# power.net
KiCad netlist of a schematic drawn in Altium Designer
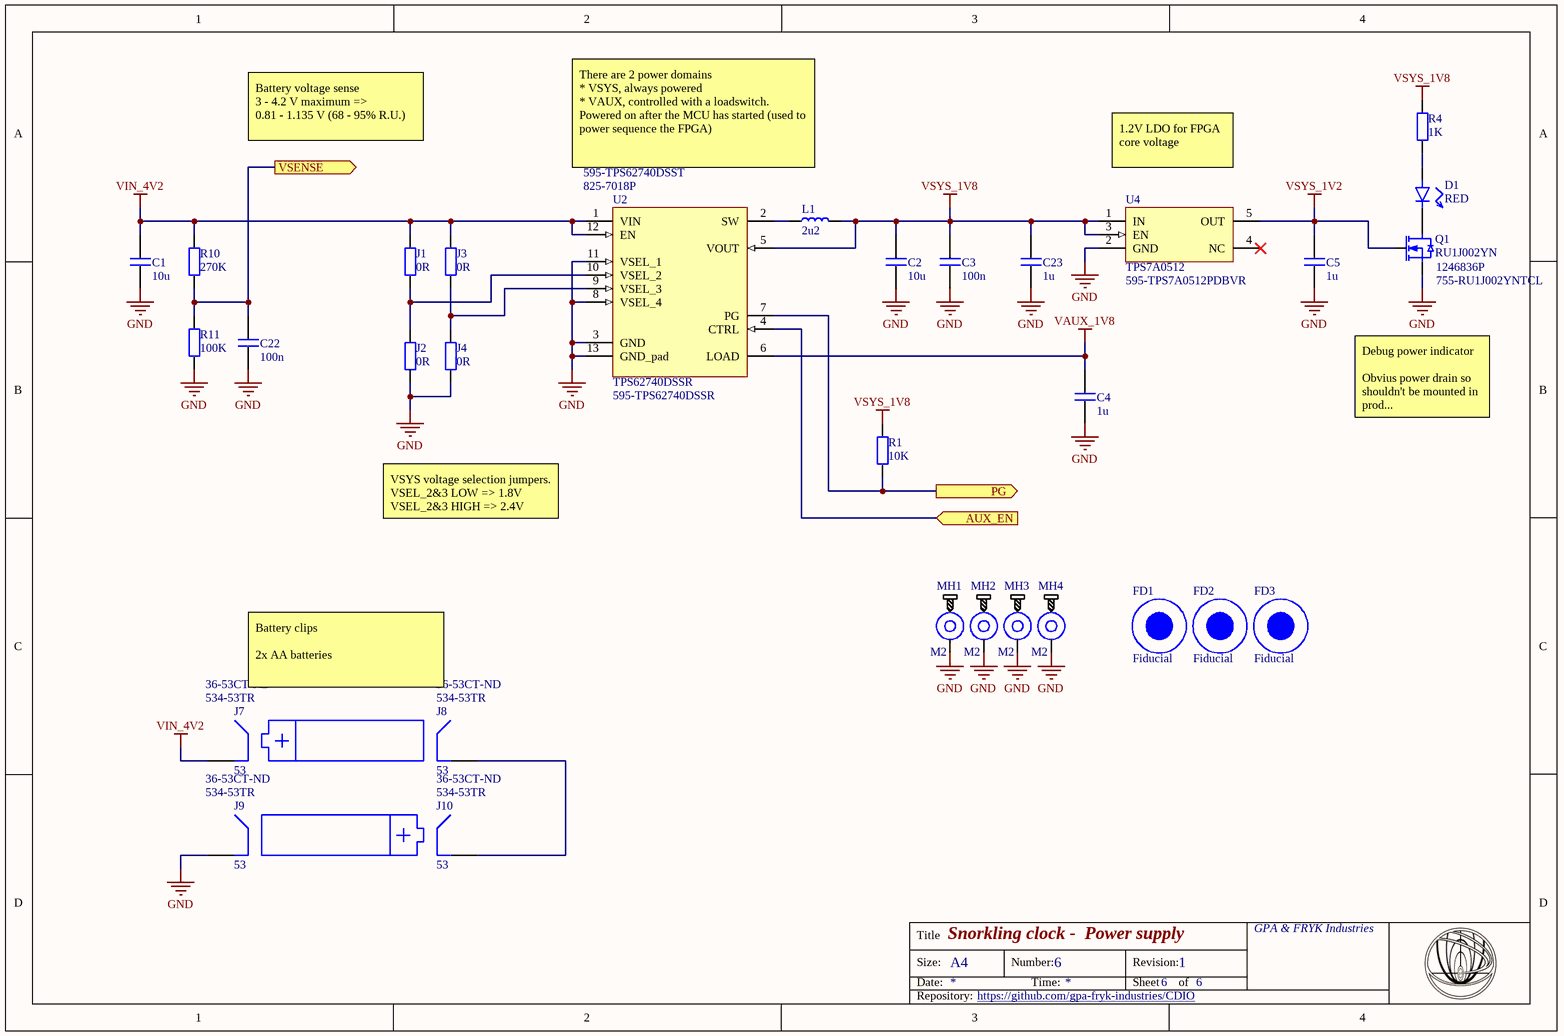
[diagram p0: power.SchDoc]

(export (version "E")
  (design (tool "Eeschema 10.0.6"))
  (components
    (comp (ref "C1")
      (value "10u")
      (footprint "CAPC3216X14N")
      (description "Capacitor")
      (fields (field (name "Comment") "cap"))
      (libsource (lib "lib_passives") (part "cap"))
    )
    (comp (ref "C2")
      (value "10u")
      (footprint "CAPC3216X14N")
      (description "Capacitor")
      (fields (field (name "Comment") "cap"))
      (libsource (lib "lib_passives") (part "cap"))
    )
    (comp (ref "C3")
      (value "100n")
      (footprint "CAPC1005X06N")
      (description "Capacitor")
      (fields (field (name "Comment") "cap"))
      (libsource (lib "lib_passives") (part "cap"))
    )
    (comp (ref "C4")
      (value "1u")
      (footprint "CAPC2012X11N")
      (description "Capacitor")
      (fields (field (name "Comment") "cap"))
      (libsource (lib "lib_passives") (part "cap"))
    )
    (comp (ref "C5")
      (value "1u")
      (footprint "CAPC2012X11N")
      (description "Capacitor")
      (fields (field (name "Comment") "cap"))
      (libsource (lib "lib_passives") (part "cap"))
    )
    (comp (ref "C22")
      (value "100n")
      (footprint "CAPC1005X06N")
      (description "Capacitor")
      (fields (field (name "Comment") "cap"))
      (libsource (lib "lib_passives") (part "cap"))
    )
    (comp (ref "C23")
      (value "1u")
      (footprint "CAPC2012X11N")
      (description "Capacitor")
      (fields (field (name "Comment") "cap"))
      (libsource (lib "lib_passives") (part "cap"))
    )
    (comp (ref "D1")
      (value "RED")
      (footprint "CAPCP1005X06N")
      (description "LED")
      (fields (field (name "Comment") "led"))
      (libsource (lib "lib_actives") (part "led"))
    )
    (comp (ref "FD1")
      (value "Fiducial")
      (footprint "fiducial_1_3")
      (libsource (lib "lib_mechanical") (part "fiducial"))
    )
    (comp (ref "FD2")
      (value "Fiducial")
      (footprint "fiducial_1_3")
      (libsource (lib "lib_mechanical") (part "fiducial"))
    )
    (comp (ref "FD3")
      (value "Fiducial")
      (footprint "fiducial_1_3")
      (libsource (lib "lib_mechanical") (part "fiducial"))
    )
    (comp (ref "J1")
      (value "0R")
      (footprint "RESC1005X04N")
      (description "Resistor")
      (fields (field (name "Comment") "res"))
      (libsource (lib "lib_passives") (part "res"))
    )
    (comp (ref "J2")
      (value "0R")
      (footprint "RESC1005X04N")
      (description "Resistor")
      (fields (field (name "Comment") "res"))
      (libsource (lib "lib_passives") (part "res"))
    )
    (comp (ref "J3")
      (value "0R")
      (footprint "RESC1005X04N")
      (description "Resistor")
      (fields (field (name "Comment") "res"))
      (libsource (lib "lib_passives") (part "res"))
    )
    (comp (ref "J4")
      (value "0R")
      (footprint "RESC1005X04N")
      (description "Resistor")
      (fields (field (name "Comment") "res"))
      (libsource (lib "lib_passives") (part "res"))
    )
    (comp (ref "J7")
      (value "53")
      (footprint "ke53")
      (description "Cylindrical Battery Contacts, Clips, Holders & Springs SMT Battery clip FOR AA")
      (fields
        (field (name "SUPPLIER PART NUMBER 1") "534-53TR")
        (field (name "SUPPLIER PART NUMBER 2") "36-53CT-ND")
      )
      (libsource (lib "lib_keystone") (part "ke53"))
    )
    (comp (ref "J8")
      (value "53")
      (footprint "ke53")
      (description "Cylindrical Battery Contacts, Clips, Holders & Springs SMT Battery clip FOR AA")
      (fields
        (field (name "SUPPLIER PART NUMBER 1") "534-53TR")
        (field (name "SUPPLIER PART NUMBER 2") "36-53CT-ND")
      )
      (libsource (lib "lib_keystone") (part "ke53"))
    )
    (comp (ref "J9")
      (value "53")
      (footprint "ke53")
      (description "Cylindrical Battery Contacts, Clips, Holders & Springs SMT Battery clip FOR AA")
      (fields
        (field (name "SUPPLIER PART NUMBER 1") "534-53TR")
        (field (name "SUPPLIER PART NUMBER 2") "36-53CT-ND")
      )
      (libsource (lib "lib_keystone") (part "ke53"))
    )
    (comp (ref "J10")
      (value "53")
      (footprint "ke53")
      (description "Cylindrical Battery Contacts, Clips, Holders & Springs SMT Battery clip FOR AA")
      (fields
        (field (name "SUPPLIER PART NUMBER 1") "534-53TR")
        (field (name "SUPPLIER PART NUMBER 2") "36-53CT-ND")
      )
      (libsource (lib "lib_keystone") (part "ke53"))
    )
    (comp (ref "L1")
      (value "2u2")
      (footprint "INDC3216X20N")
      (description "Inductor")
      (fields (field (name "Comment") "ind"))
      (libsource (lib "lib_passives") (part "ind"))
    )
    (comp (ref "MH1")
      (value "M2")
      (footprint "mount_m2l")
      (description "Mounting hole")
      (libsource (lib "lib_mechanical") (part "mounting_hole"))
    )
    (comp (ref "MH2")
      (value "M2")
      (footprint "mount_m2l")
      (description "Mounting hole")
      (libsource (lib "lib_mechanical") (part "mounting_hole"))
    )
    (comp (ref "MH3")
      (value "M2")
      (footprint "mount_m2l")
      (description "Mounting hole")
      (libsource (lib "lib_mechanical") (part "mounting_hole"))
    )
    (comp (ref "MH4")
      (value "M2")
      (footprint "mount_m2l")
      (description "Mounting hole")
      (libsource (lib "lib_mechanical") (part "mounting_hole"))
    )
    (comp (ref "Q1")
      (value "RU1J002YN")
      (footprint "SOTFL65P210X105-3N")
      (description "N-channel 50V 200mA Small signal MOSFET")
      (fields
        (field (name "SUPPLIER PART NUMBER 1") "1246836P")
        (field (name "SUPPLIER PART NUMBER 2") "755-RU1J002YNTCL")
      )
      (libsource (lib "lib_rohm") (part "ru1j002yn"))
    )
    (comp (ref "R1")
      (value "10K")
      (footprint "RESC1005X04N")
      (description "Resistor")
      (fields (field (name "Comment") "res"))
      (libsource (lib "lib_passives") (part "res"))
    )
    (comp (ref "R4")
      (value "1K")
      (footprint "RESC1005X04N")
      (description "Resistor")
      (fields (field (name "Comment") "res"))
      (libsource (lib "lib_passives") (part "res"))
    )
    (comp (ref "R10")
      (value "270K")
      (footprint "RESC1005X04N")
      (description "Resistor")
      (fields (field (name "Comment") "res"))
      (libsource (lib "lib_passives") (part "res"))
    )
    (comp (ref "R11")
      (value "100K")
      (footprint "RESC1005X04N")
      (description "Resistor")
      (fields (field (name "Comment") "res"))
      (libsource (lib "lib_passives") (part "res"))
    )
    (comp (ref "U2")
      (value "TPS62740DSSR")
      (footprint "SON50P200X80_HS-13N")
      (description "TPS6274x 360nA IQ Step Down Converter For Low Power Applications")
      (fields
        (field (name "SUPPLIER PART NUMBER 1") "595-TPS62740DSSR")
        (field (name "SUPPLIER PART NUMBER 2") "825-7018P")
        (field (name "SUPPLIER PART NUMBER 3") "595-TPS62740DSST")
      )
      (libsource (lib "lib_ti") (part "tps62740dssr"))
    )
    (comp (ref "U4")
      (value "TPS7A0512")
      (footprint "SOT95P280X145-5N")
      (description "TPS7A05 1-µA Ultralow IQ, 200-mA, Low-Dropout Regulator")
      (fields (field (name "SUPPLIER PART NUMBER 1") "595-TPS7A0512PDBVR"))
      (libsource (lib "lib_ti") (part "tps7a0512pdbvr"))
    )
  )
  (nets
    (net (code "1") (name "/AUX_EN") (class "Default")
      (node (ref "U2") (pin "4") (pinfunction "CTRL_4") (pintype "input"))
    )
    (net (code "2") (name "/PG") (class "Default")
      (node (ref "R1") (pin "1") (pinfunction "1_1") (pintype "passive"))
      (node (ref "U2") (pin "7") (pinfunction "PG_7") (pintype "open_collector"))
    )
    (net (code "3") (name "/VSENSE") (class "Default")
      (node (ref "C22") (pin "2") (pinfunction "2_2") (pintype "passive"))
      (node (ref "R10") (pin "1") (pinfunction "1_1") (pintype "passive"))
      (node (ref "R11") (pin "2") (pinfunction "2_2") (pintype "passive"))
    )
    (net (code "4") (name "GND") (class "Default")
      (node (ref "C1") (pin "1") (pinfunction "1_1") (pintype "passive"))
      (node (ref "C2") (pin "1") (pinfunction "1_1") (pintype "passive"))
      (node (ref "C22") (pin "1") (pinfunction "1_1") (pintype "passive"))
      (node (ref "C23") (pin "1") (pinfunction "1_1") (pintype "passive"))
      (node (ref "C3") (pin "1") (pinfunction "1_1") (pintype "passive"))
      (node (ref "C4") (pin "1") (pinfunction "1_1") (pintype "passive"))
      (node (ref "C5") (pin "1") (pinfunction "1_1") (pintype "passive"))
      (node (ref "J2") (pin "1") (pinfunction "1_1") (pintype "passive"))
      (node (ref "J4") (pin "1") (pinfunction "1_1") (pintype "passive"))
      (node (ref "J9") (pin "1") (pinfunction "1_1") (pintype "passive"))
      (node (ref "MH1") (pin "1") (pinfunction "1_1") (pintype "passive"))
      (node (ref "MH2") (pin "1") (pinfunction "1_1") (pintype "passive"))
      (node (ref "MH3") (pin "1") (pinfunction "1_1") (pintype "passive"))
      (node (ref "MH4") (pin "1") (pinfunction "1_1") (pintype "passive"))
      (node (ref "Q1") (pin "2") (pinfunction "S_2") (pintype "passive"))
      (node (ref "R11") (pin "1") (pinfunction "1_1") (pintype "passive"))
      (node (ref "U2") (pin "11") (pinfunction "VSEL_1_11") (pintype "input"))
      (node (ref "U2") (pin "13") (pinfunction "GND_pad_13") (pintype "power_in"))
      (node (ref "U2") (pin "3") (pinfunction "GND_3") (pintype "power_in"))
      (node (ref "U2") (pin "8") (pinfunction "VSEL_4_8") (pintype "input"))
      (node (ref "U4") (pin "2") (pinfunction "GND_2") (pintype "power_in"))
    )
    (net (code "5") (name "Net-(D1-PadA)") (class "Default")
      (node (ref "D1") (pin "A") (pinfunction "A_A") (pintype "passive"))
      (node (ref "R4") (pin "1") (pinfunction "1_1") (pintype "passive"))
    )
    (net (code "6") (name "Net-(J10-Pad1)") (class "Default")
      (node (ref "J10") (pin "1") (pinfunction "1_1") (pintype "passive"))
      (node (ref "J8") (pin "1") (pinfunction "1_1") (pintype "passive"))
    )
    (net (code "7") (name "Net-(Q1-D)") (class "Default")
      (node (ref "D1") (pin "C") (pinfunction "C_C") (pintype "passive"))
      (node (ref "Q1") (pin "3") (pinfunction "D_3") (pintype "passive"))
    )
    (net (code "8") (name "Net-(U2-SW)") (class "Default")
      (node (ref "L1") (pin "1") (pinfunction "1_1") (pintype "passive"))
      (node (ref "U2") (pin "2") (pinfunction "SW_2") (pintype "power_in"))
    )
    (net (code "9") (name "Net-(U2-VSEL_2)") (class "Default")
      (node (ref "J1") (pin "1") (pinfunction "1_1") (pintype "passive"))
      (node (ref "J2") (pin "2") (pinfunction "2_2") (pintype "passive"))
      (node (ref "U2") (pin "10") (pinfunction "VSEL_2_10") (pintype "input"))
    )
    (net (code "10") (name "Net-(U2-VSEL_3)") (class "Default")
      (node (ref "J3") (pin "1") (pinfunction "1_1") (pintype "passive"))
      (node (ref "J4") (pin "2") (pinfunction "2_2") (pintype "passive"))
      (node (ref "U2") (pin "9") (pinfunction "VSEL_3_9") (pintype "input"))
    )
    (net (code "11") (name "VAUX_1V8") (class "Default")
      (node (ref "C4") (pin "2") (pinfunction "2_2") (pintype "passive"))
      (node (ref "U2") (pin "6") (pinfunction "LOAD_6") (pintype "power_in"))
    )
    (net (code "12") (name "VIN_4V2") (class "Default")
      (node (ref "C1") (pin "2") (pinfunction "2_2") (pintype "passive"))
      (node (ref "J1") (pin "2") (pinfunction "2_2") (pintype "passive"))
      (node (ref "J3") (pin "2") (pinfunction "2_2") (pintype "passive"))
      (node (ref "J7") (pin "1") (pinfunction "1_1") (pintype "passive"))
      (node (ref "R10") (pin "2") (pinfunction "2_2") (pintype "passive"))
      (node (ref "U2") (pin "1") (pinfunction "VIN_1") (pintype "power_in"))
      (node (ref "U2") (pin "12") (pinfunction "EN_12") (pintype "input"))
    )
    (net (code "13") (name "VSYS_1V2") (class "Default")
      (node (ref "C5") (pin "2") (pinfunction "2_2") (pintype "passive"))
      (node (ref "Q1") (pin "1") (pinfunction "G_1") (pintype "passive"))
      (node (ref "U4") (pin "5") (pinfunction "OUT_5") (pintype "power_in"))
    )
    (net (code "14") (name "VSYS_1V8") (class "Default")
      (node (ref "C2") (pin "2") (pinfunction "2_2") (pintype "passive"))
      (node (ref "C23") (pin "2") (pinfunction "2_2") (pintype "passive"))
      (node (ref "C3") (pin "2") (pinfunction "2_2") (pintype "passive"))
      (node (ref "L1") (pin "2") (pinfunction "2_2") (pintype "passive"))
      (node (ref "R1") (pin "2") (pinfunction "2_2") (pintype "passive"))
      (node (ref "R4") (pin "2") (pinfunction "2_2") (pintype "passive"))
      (node (ref "U2") (pin "5") (pinfunction "VOUT_5") (pintype "input"))
      (node (ref "U4") (pin "1") (pinfunction "IN_1") (pintype "power_in"))
      (node (ref "U4") (pin "3") (pinfunction "EN_3") (pintype "input"))
    )
    (net (code "15") (name "unconnected-(U4-NC-Pad4)") (class "Default")
      (node (ref "U4") (pin "4") (pinfunction "NC_4") (pintype "passive+no_connect"))
    )
  )
)
